# ltk-mw-tx.net
KiCad netlist of a schematic drawn in Altium Designer
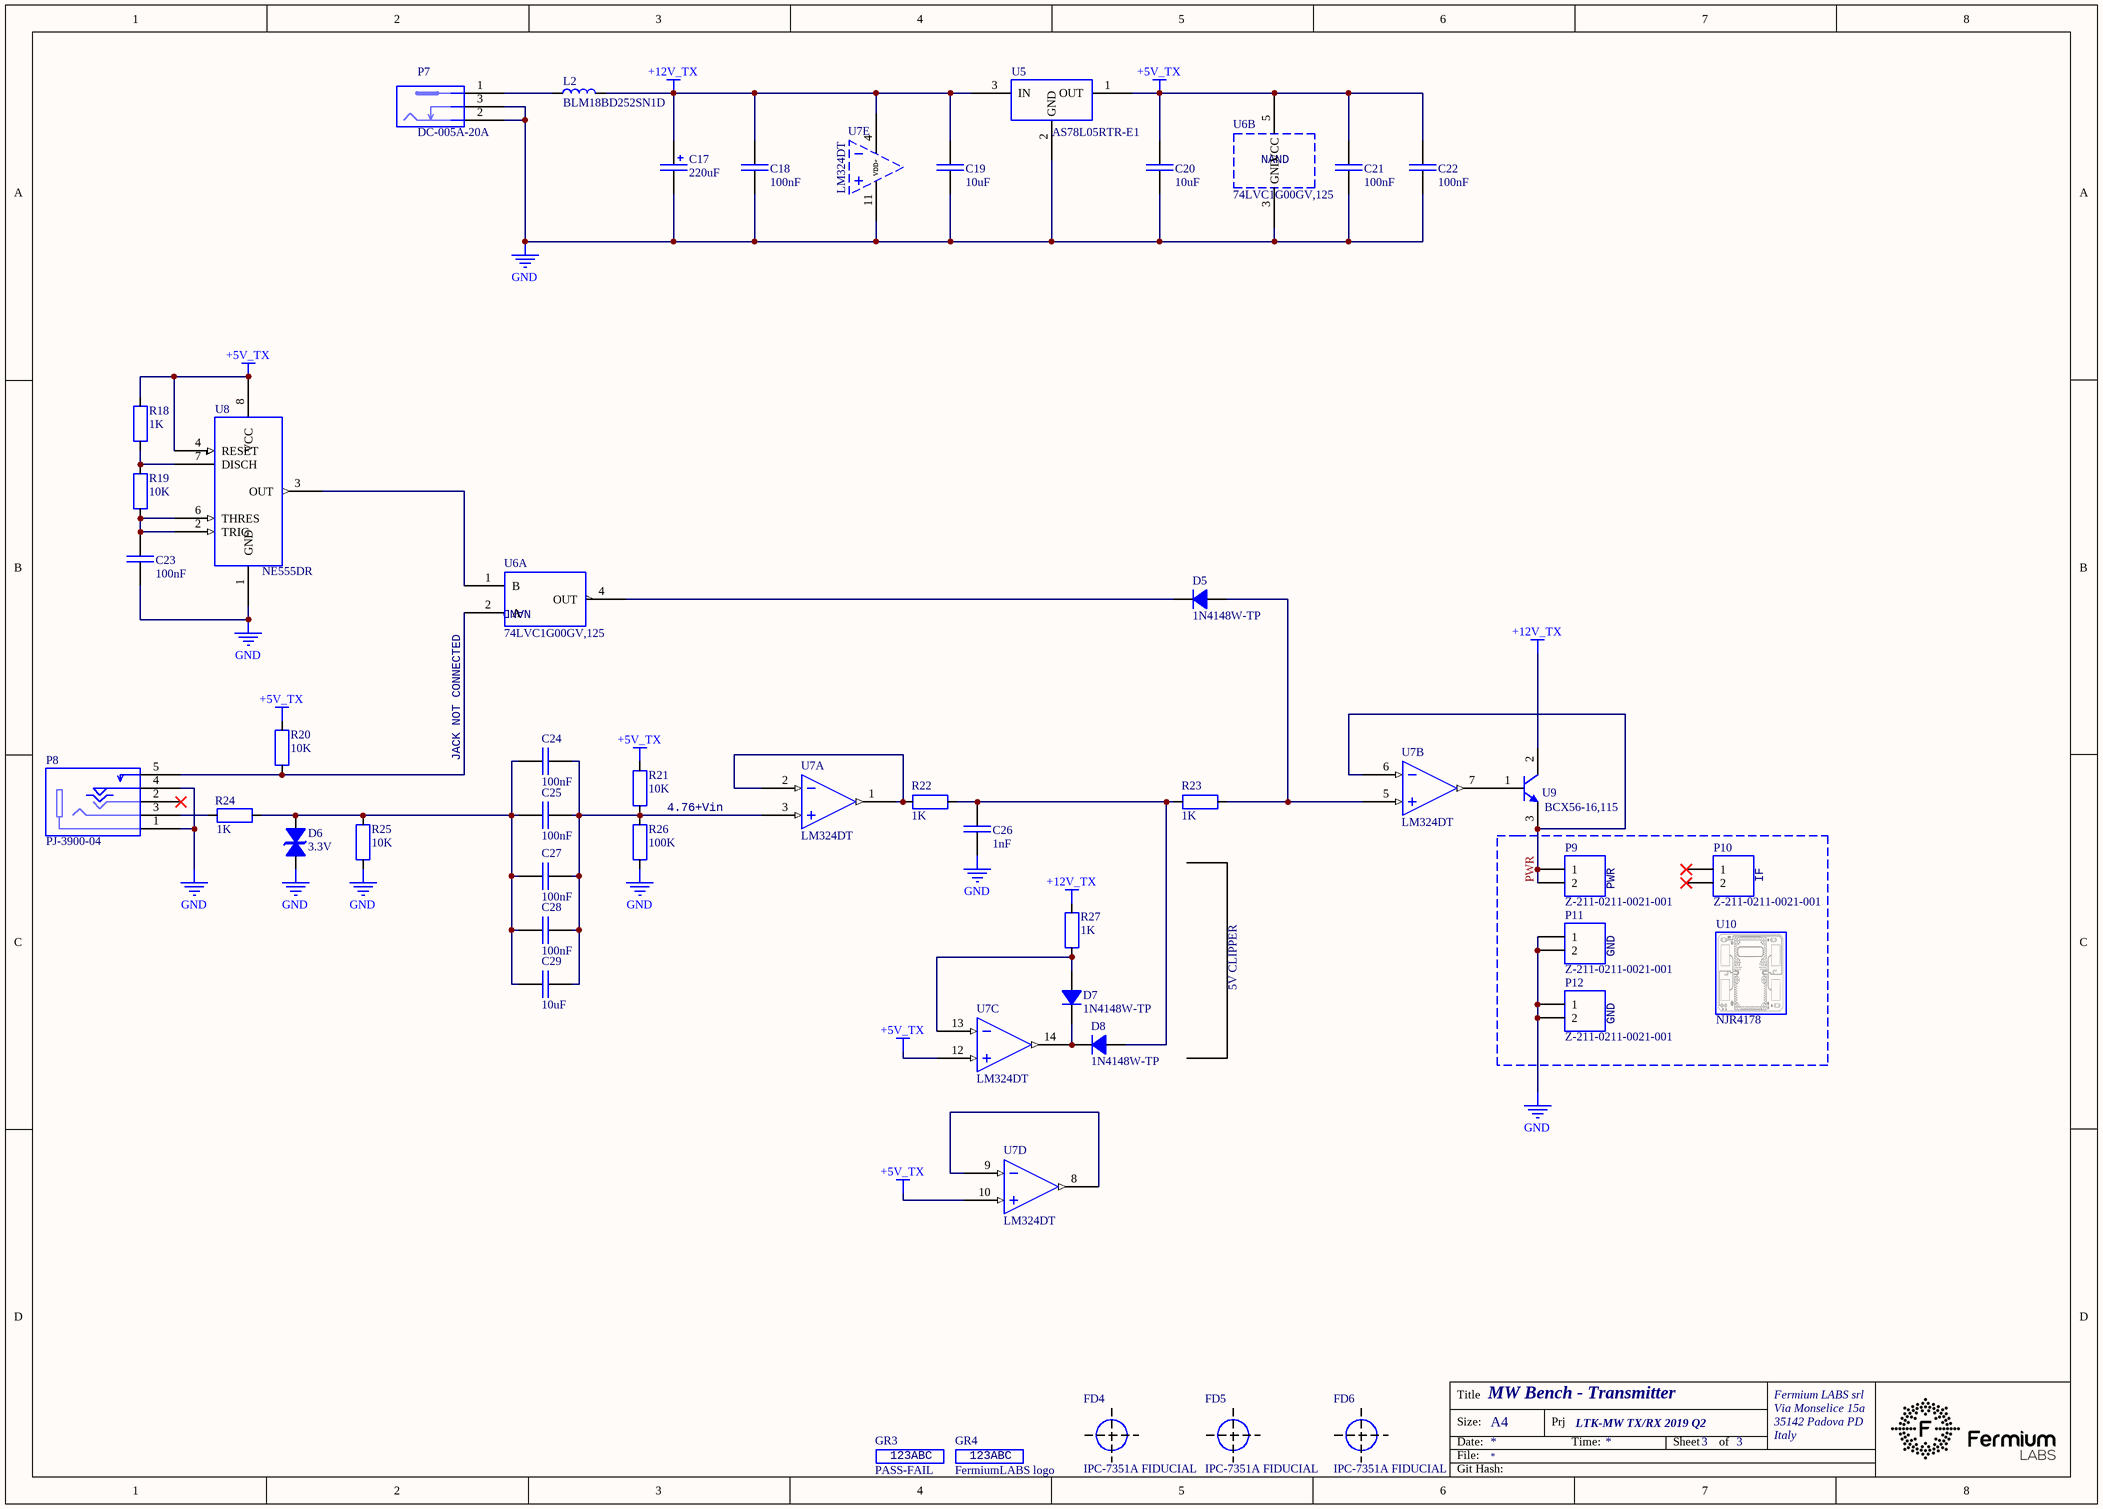
[diagram p0: ltk-mw-tx.SchDoc]

(export (version "E")
  (design (tool "Eeschema 10.0.6"))
  (components
    (comp (ref "C17")
      (value "220uF")
      (footprint "3924B366-8672-45E9-B0BE-62DACC24E783")
      (description "CAP  THT ELEC 220uF 25V 20%")
      (fields (field (name "PART NUMBER") "1a28df19-6d3e-4a71-836c-f22920f8e8ab"))
      (libsource (lib "frmdblib") (part "GENERIC_C_ELEC"))
    )
    (comp (ref "C18")
      (value "100nF")
      (footprint "CAP 0603_1608")
      (description "CAP SMD MLCC 100nF 25V 0603 X7R")
      (fields (field (name "PART NUMBER") "02841f84-ac15-41b5-9e17-915f8f067828"))
      (libsource (lib "frmdblib") (part "GENERIC_C"))
    )
    (comp (ref "C19")
      (value "10uF")
      (footprint "CAP 0805_2012")
      (description "CAP SMD MLCC 10uF 25V 0805 X5R")
      (fields (field (name "PART NUMBER") "1ffbe5a9-0884-4740-bdad-20a6a98400e6"))
      (libsource (lib "frmdblib") (part "GENERIC_C"))
    )
    (comp (ref "C20")
      (value "10uF")
      (footprint "CAP 0805_2012")
      (description "CAP SMD MLCC 10uF 25V 0805 X5R")
      (fields (field (name "PART NUMBER") "1ffbe5a9-0884-4740-bdad-20a6a98400e6"))
      (libsource (lib "frmdblib") (part "GENERIC_C"))
    )
    (comp (ref "C21")
      (value "100nF")
      (footprint "CAP 0603_1608")
      (description "CAP SMD MLCC 100nF 25V 0603 X7R")
      (fields (field (name "PART NUMBER") "02841f84-ac15-41b5-9e17-915f8f067828"))
      (libsource (lib "frmdblib") (part "GENERIC_C"))
    )
    (comp (ref "C22")
      (value "100nF")
      (footprint "CAP 0603_1608")
      (description "CAP SMD MLCC 100nF 25V 0603 X7R")
      (fields (field (name "PART NUMBER") "02841f84-ac15-41b5-9e17-915f8f067828"))
      (libsource (lib "frmdblib") (part "GENERIC_C"))
    )
    (comp (ref "C23")
      (value "100nF")
      (footprint "CAP 0603_1608")
      (description "CAP SMD MLCC 100nF 25V 0603 X7R")
      (fields (field (name "PART NUMBER") "02841f84-ac15-41b5-9e17-915f8f067828"))
      (libsource (lib "frmdblib") (part "GENERIC_C"))
    )
    (comp (ref "C24")
      (value "100nF")
      (footprint "CAP 0603_1608")
      (description "CAP SMD MLCC 100nF 25V 0603 X7R")
      (fields (field (name "PART NUMBER") "02841f84-ac15-41b5-9e17-915f8f067828"))
      (libsource (lib "frmdblib") (part "GENERIC_C"))
    )
    (comp (ref "C25")
      (value "100nF")
      (footprint "CAP 0603_1608")
      (description "CAP SMD MLCC 100nF 25V 0603 X7R")
      (fields (field (name "PART NUMBER") "02841f84-ac15-41b5-9e17-915f8f067828"))
      (libsource (lib "frmdblib") (part "GENERIC_C"))
    )
    (comp (ref "C26")
      (value "1nF")
      (footprint "CAP 0603_1608")
      (description "CAP SMD MLCC 1nF 50V 0603 X7R")
      (fields (field (name "PART NUMBER") "0eca2548-3630-4fea-a3d5-94248c1cae74"))
      (libsource (lib "frmdblib") (part "GENERIC_C"))
    )
    (comp (ref "C27")
      (value "100nF")
      (footprint "CAP 0603_1608")
      (description "CAP SMD MLCC 100nF 25V 0603 X7R")
      (fields (field (name "PART NUMBER") "02841f84-ac15-41b5-9e17-915f8f067828"))
      (libsource (lib "frmdblib") (part "GENERIC_C"))
    )
    (comp (ref "C28")
      (value "100nF")
      (footprint "CAP 0603_1608")
      (description "CAP SMD MLCC 100nF 25V 0603 X7R")
      (fields (field (name "PART NUMBER") "02841f84-ac15-41b5-9e17-915f8f067828"))
      (libsource (lib "frmdblib") (part "GENERIC_C"))
    )
    (comp (ref "C29")
      (value "10uF")
      (footprint "CAP 0805_2012")
      (description "CAP SMD MLCC 10uF 25V 0805 X5R")
      (fields (field (name "PART NUMBER") "1ffbe5a9-0884-4740-bdad-20a6a98400e6"))
      (libsource (lib "frmdblib") (part "GENERIC_C"))
    )
    (comp (ref "D5")
      (value "1N4148W-TP")
      (footprint "SOD-123")
      (description "DIODE SMD 100V 150mA 1.5Vf SOD-123 4148")
      (fields (field (name "PART NUMBER") "5e920700-75df-48e3-84dd-8f9f777caed8"))
      (libsource (lib "frmdblib") (part "GENERIC_D"))
    )
    (comp (ref "D6")
      (value "3.3V")
      (footprint "SOD523F")
      (description "DIODE SMD TVS 3.3V BIDIRECTIONAL SOD-523")
      (fields (field (name "PART NUMBER") "d6266fd0-7428-4fb9-a062-338cdce926fd"))
      (libsource (lib "frmdblib") (part "GENERIC_D_TVS_BI"))
    )
    (comp (ref "D7")
      (value "1N4148W-TP")
      (footprint "SOD-123")
      (description "DIODE SMD 100V 150mA 1.5Vf SOD-123 4148")
      (fields (field (name "PART NUMBER") "5e920700-75df-48e3-84dd-8f9f777caed8"))
      (libsource (lib "frmdblib") (part "GENERIC_D"))
    )
    (comp (ref "D8")
      (value "1N4148W-TP")
      (footprint "SOD-123")
      (description "DIODE SMD 100V 150mA 1.5Vf SOD-123 4148")
      (fields (field (name "PART NUMBER") "5e920700-75df-48e3-84dd-8f9f777caed8"))
      (libsource (lib "frmdblib") (part "GENERIC_D"))
    )
    (comp (ref "FD4")
      (value "IPC-7351A FIDUCIAL")
      (footprint "FIDUCIAL-IPC-7351A")
      (description "GRAPHICS FIDUCIAL IPC-7351A")
      (fields (field (name "PART NUMBER") "19da4612-eb95-43bb-9984-553a52b2a224"))
      (libsource (lib "frmdblib") (part "GENERIC_FIDUCIAL"))
    )
    (comp (ref "FD5")
      (value "IPC-7351A FIDUCIAL")
      (footprint "FIDUCIAL-IPC-7351A")
      (description "GRAPHICS FIDUCIAL IPC-7351A")
      (fields (field (name "PART NUMBER") "19da4612-eb95-43bb-9984-553a52b2a224"))
      (libsource (lib "frmdblib") (part "GENERIC_FIDUCIAL"))
    )
    (comp (ref "FD6")
      (value "IPC-7351A FIDUCIAL")
      (footprint "FIDUCIAL-IPC-7351A")
      (description "GRAPHICS FIDUCIAL IPC-7351A")
      (fields (field (name "PART NUMBER") "19da4612-eb95-43bb-9984-553a52b2a224"))
      (libsource (lib "frmdblib") (part "GENERIC_FIDUCIAL"))
    )
    (comp (ref "GR3")
      (value "PASS-FAIL")
      (footprint "0B1556B7-A534-4801-B57D-01EFA34B1205")
      (description "GRAPHICS PASS-FAIL MARK")
      (fields (field (name "PART NUMBER") "d1abe19f-3fed-4f20-b2ed-afc0ffbc6628"))
      (libsource (lib "frmdblib") (part "GENERIC_GRAPHIC"))
    )
    (comp (ref "GR4")
      (value "FermiumLABS logo")
      (footprint "5394DE47-A0E8-4329-8464-7791B7C19310")
      (description "GRAPHICS LOGO FERMIUM LABS SRL")
      (fields (field (name "PART NUMBER") "50f8ea88-0034-49fe-a263-d8e97bc35e2f"))
      (libsource (lib "frmdblib") (part "GENERIC_GRAPHIC"))
    )
    (comp (ref "L2")
      (value "BLM18BD252SN1D")
      (footprint "FER 0603_1608")
      (description "FER SMD CHIP 0603 400mA 1k@100MHz 500mOhm")
      (fields (field (name "PART NUMBER") "c9e30ae8-9d5b-4135-a079-b1147da846d8"))
      (libsource (lib "frmdblib") (part "GENERIC_L"))
    )
    (comp (ref "P7")
      (value "DC-005A-20A")
      (footprint "F0972D8A-C5C0-4A84-836D-A9666EE65C2D")
      (description "CONN THT DC JACK 0.5A 30VDC 5Kcycles")
      (fields (field (name "PART NUMBER") "b53db51a-1725-412b-9039-fa7a45c7c438"))
      (libsource (lib "frmdblib") (part "34A1CD0B-E262-46EF-B9F1-39CB809C308F"))
    )
    (comp (ref "P8")
      (value "PJ-3900-04")
      (footprint "7EF2B92C-0FC9-4C85-B662-5CEC65BFCCC4")
      (description "CONN THT 3.5mm AUDIO STEREO AUX SWITCH")
      (fields (field (name "PART NUMBER") "80507a24-5d7c-4cf5-953e-f54832d54564"))
      (libsource (lib "frmdblib") (part "46E41D2F-79BD-46AC-B778-70B2D50A946A"))
    )
    (comp (ref "P9")
      (value "Z-211-0211-0021-001")
      (footprint "0FBEB40D-2B6D-43C7-945F-A2D40A82B953")
      (description "CONN THT PIN HEADER 2P MALE 2.54mm")
      (fields (field (name "PART NUMBER") "fb9043ef-1dd5-4a9c-8c1a-da0c667690ac"))
      (libsource (lib "frmdblib") (part "Header 2"))
    )
    (comp (ref "P10")
      (value "Z-211-0211-0021-001")
      (footprint "0FBEB40D-2B6D-43C7-945F-A2D40A82B953")
      (description "CONN THT PIN HEADER 2P MALE 2.54mm")
      (fields (field (name "PART NUMBER") "fb9043ef-1dd5-4a9c-8c1a-da0c667690ac"))
      (libsource (lib "frmdblib") (part "Header 2"))
    )
    (comp (ref "P11")
      (value "Z-211-0211-0021-001")
      (footprint "0FBEB40D-2B6D-43C7-945F-A2D40A82B953")
      (description "CONN THT PIN HEADER 2P MALE 2.54mm")
      (fields (field (name "PART NUMBER") "fb9043ef-1dd5-4a9c-8c1a-da0c667690ac"))
      (libsource (lib "frmdblib") (part "Header 2"))
    )
    (comp (ref "P12")
      (value "Z-211-0211-0021-001")
      (footprint "0FBEB40D-2B6D-43C7-945F-A2D40A82B953")
      (description "CONN THT PIN HEADER 2P MALE 2.54mm")
      (fields (field (name "PART NUMBER") "fb9043ef-1dd5-4a9c-8c1a-da0c667690ac"))
      (libsource (lib "frmdblib") (part "Header 2"))
    )
    (comp (ref "R18")
      (value "1K")
      (footprint "RES 0603_1608")
      (description "RES SMD 1K OHM 1% 1/10W 0603")
      (fields (field (name "PART NUMBER") "a678220f-9e9d-4863-a833-9993504f723c"))
      (libsource (lib "frmdblib") (part "GENERIC_R"))
    )
    (comp (ref "R19")
      (value "10K")
      (footprint "RES 0603_1608")
      (description "RES SMD 10K OHM 1% 1/10W 0603")
      (fields (field (name "PART NUMBER") "93242766-ba1d-462d-b58f-ce1dfc4129c8"))
      (libsource (lib "frmdblib") (part "GENERIC_R"))
    )
    (comp (ref "R20")
      (value "10K")
      (footprint "RES 0603_1608")
      (description "RES SMD 10K OHM 1% 1/10W 0603")
      (fields (field (name "PART NUMBER") "93242766-ba1d-462d-b58f-ce1dfc4129c8"))
      (libsource (lib "frmdblib") (part "GENERIC_R"))
    )
    (comp (ref "R21")
      (value "10K")
      (footprint "RES 0603_1608")
      (description "RES SMD 10K OHM 1% 1/10W 0603")
      (fields (field (name "PART NUMBER") "93242766-ba1d-462d-b58f-ce1dfc4129c8"))
      (libsource (lib "frmdblib") (part "GENERIC_R"))
    )
    (comp (ref "R22")
      (value "1K")
      (footprint "RES 0603_1608")
      (description "RES SMD 1K OHM 1% 1/10W 0603")
      (fields (field (name "PART NUMBER") "a678220f-9e9d-4863-a833-9993504f723c"))
      (libsource (lib "frmdblib") (part "GENERIC_R"))
    )
    (comp (ref "R23")
      (value "1K")
      (footprint "RES 0603_1608")
      (description "RES SMD 1K OHM 1% 1/10W 0603")
      (fields (field (name "PART NUMBER") "a678220f-9e9d-4863-a833-9993504f723c"))
      (libsource (lib "frmdblib") (part "GENERIC_R"))
    )
    (comp (ref "R24")
      (value "1K")
      (footprint "RES 0603_1608")
      (description "RES SMD 1K OHM 1% 1/10W 0603")
      (fields (field (name "PART NUMBER") "a678220f-9e9d-4863-a833-9993504f723c"))
      (libsource (lib "frmdblib") (part "GENERIC_R"))
    )
    (comp (ref "R25")
      (value "10K")
      (footprint "RES 0603_1608")
      (description "RES SMD 10K OHM 1% 1/10W 0603")
      (fields (field (name "PART NUMBER") "93242766-ba1d-462d-b58f-ce1dfc4129c8"))
      (libsource (lib "frmdblib") (part "GENERIC_R"))
    )
    (comp (ref "R26")
      (value "100K")
      (footprint "RES 0603_1608")
      (description "RES SMD 100K OHM 1% 1/10W 0603")
      (fields (field (name "PART NUMBER") "76af10b3-9d85-4b5c-a2d6-26cc74f432f7"))
      (libsource (lib "frmdblib") (part "GENERIC_R"))
    )
    (comp (ref "R27")
      (value "1K")
      (footprint "RES 0603_1608")
      (description "RES SMD 1K OHM 1% 1/10W 0603")
      (fields (field (name "PART NUMBER") "a678220f-9e9d-4863-a833-9993504f723c"))
      (libsource (lib "frmdblib") (part "GENERIC_R"))
    )
    (comp (ref "U5")
      (value "AS78L05RTR-E1")
      (footprint "E733EFB9-FE91-4AE9-9197-29251971C3DC")
      (description "IC SMD LINEAR VOLTAGE REGULATOR 5V 100mA SOT-89")
      (fields (field (name "PART NUMBER") "fd64863e-487f-4688-b264-696c0ba5456b"))
      (libsource (lib "frmdblib") (part "FCB39772-D6AF-4D61-BC58-A46A50428B6B"))
    )
    (comp (ref "U6")
      (value "74LVC1G00GV,125")
      (footprint "9B4F62E8-D129-4139-99C7-3E5580D0C4B3")
      (description "IC SMD NAND GATE 2 INPUTS 74X00 SC-74A")
      (fields (field (name "PART NUMBER") "33900555-dbb4-4b72-871f-952983a59b08"))
      (libsource (lib "frmdblib") (part "2A82CEC3-2DF5-4DD3-9AA0-8AD0F8FDAF27"))
    )
    (comp (ref "U7")
      (value "LM324DT")
      (footprint "34355DA5-B1DA-47C2-A88A-ECF82120A4F7")
      (description "IC SMD OPAMP LM324DT SO-14")
      (fields (field (name "PART NUMBER") "21a85167-c328-42f7-a52e-365842c6dad3"))
      (libsource (lib "frmdblib") (part "B8DB4B19-8E9C-4F46-A390-7A352E041443"))
    )
    (comp (ref "U8")
      (value "NE555DR")
      (footprint "TI SOIC-8 D")
      (description "IC SMD TIMER NE555 SOIC-8")
      (fields (field (name "PART NUMBER") "d16ab88a-2543-469a-8940-7b800b633548"))
      (libsource (lib "frmdblib") (part "3A1FF759-9FC3-4379-AD1F-76F749A75FB1"))
    )
    (comp (ref "U9")
      (value "BCX56-16,115")
      (footprint "13DB0D7C-893C-4A10-A75B-EAAEE46B398C")
      (description "TRANS NPN BCX56-16 1A 80V 1.25W SOT-89-3")
      (fields (field (name "PART NUMBER") "0e502e05-00ae-4c6f-83a4-b2f55de2403a"))
      (libsource (lib "frmdblib") (part "GENERIC_NPN_BCE"))
    )
    (comp (ref "U10")
      (value "NJR4178")
      (footprint "25B19271-CD6F-4BC8-A99B-F617D566DC9C")
      (description "MODULE THT RADAR DOPPLER 10.525GHz NJR4178")
      (fields (field (name "PART NUMBER") "f0e19a38-18de-4253-8da2-aebb0c4083bd"))
      (libsource (lib "frmdblib") (part "687D5558-C857-4646-9F75-B643D2B4D9DF"))
    )
  )
  (nets
    (net (code "1") (name "+5V_TX") (class "Default")
      (node (ref "C20") (pin "2") (pintype "passive"))
      (node (ref "C21") (pin "2") (pintype "passive"))
      (node (ref "C22") (pin "2") (pintype "passive"))
      (node (ref "R18") (pin "2") (pintype "passive"))
      (node (ref "R20") (pin "1") (pintype "passive"))
      (node (ref "R21") (pin "2") (pintype "passive"))
      (node (ref "U5") (pin "1") (pinfunction "OUT_1") (pintype "passive"))
      (node (ref "U6") (pin "5") (pinfunction "VCC_5") (pintype "passive"))
      (node (ref "U7") (pin "10") (pinfunction "IN+_10") (pintype "input"))
      (node (ref "U7") (pin "12") (pinfunction "IN+_12") (pintype "input"))
      (node (ref "U8") (pin "4") (pinfunction "RESET_4") (pintype "input"))
      (node (ref "U8") (pin "8") (pinfunction "VCC_8") (pintype "power_in"))
    )
    (net (code "2") (name "+12V_TX") (class "Default")
      (node (ref "C17") (pin "1") (pintype "passive"))
      (node (ref "C18") (pin "2") (pintype "passive"))
      (node (ref "C19") (pin "2") (pintype "passive"))
      (node (ref "L2") (pin "2") (pintype "passive"))
      (node (ref "R27") (pin "2") (pintype "passive"))
      (node (ref "U5") (pin "3") (pinfunction "IN_3") (pintype "passive"))
      (node (ref "U7") (pin "4") (pinfunction "VDD+_4") (pintype "power_in"))
      (node (ref "U9") (pin "2") (pinfunction "C_2") (pintype "passive"))
    )
    (net (code "3") (name "/PWR") (class "Default")
      (node (ref "P9") (pin "1") (pinfunction "1_1") (pintype "passive"))
      (node (ref "P9") (pin "2") (pinfunction "2_2") (pintype "passive"))
      (node (ref "U7") (pin "6") (pinfunction "IN-_6") (pintype "input"))
      (node (ref "U9") (pin "3") (pinfunction "E_3") (pintype "passive"))
    )
    (net (code "4") (name "GND") (class "Default")
      (node (ref "C17") (pin "2") (pintype "passive"))
      (node (ref "C18") (pin "1") (pintype "passive"))
      (node (ref "C19") (pin "1") (pintype "passive"))
      (node (ref "C20") (pin "1") (pintype "passive"))
      (node (ref "C21") (pin "1") (pintype "passive"))
      (node (ref "C22") (pin "1") (pintype "passive"))
      (node (ref "C23") (pin "2") (pintype "passive"))
      (node (ref "C26") (pin "2") (pintype "passive"))
      (node (ref "D6") (pin "2") (pintype "passive"))
      (node (ref "P11") (pin "1") (pinfunction "1_1") (pintype "passive"))
      (node (ref "P11") (pin "2") (pinfunction "2_2") (pintype "passive"))
      (node (ref "P12") (pin "1") (pinfunction "1_1") (pintype "passive"))
      (node (ref "P12") (pin "2") (pinfunction "2_2") (pintype "passive"))
      (node (ref "P7") (pin "2") (pinfunction "2_2") (pintype "passive"))
      (node (ref "P7") (pin "3") (pinfunction "3_3") (pintype "passive"))
      (node (ref "P8") (pin "1") (pinfunction "GND_1") (pintype "passive"))
      (node (ref "P8") (pin "4") (pinfunction "AUX_4") (pintype "passive"))
      (node (ref "R25") (pin "1") (pintype "passive"))
      (node (ref "R26") (pin "1") (pintype "passive"))
      (node (ref "U5") (pin "2") (pinfunction "GND_2") (pintype "passive"))
      (node (ref "U6") (pin "3") (pinfunction "GND_3") (pintype "passive"))
      (node (ref "U7") (pin "11") (pinfunction "VDD-_11") (pintype "power_in"))
      (node (ref "U8") (pin "1") (pinfunction "GND_1") (pintype "power_in"))
    )
    (net (code "5") (name "Net-(C24-Pad1)") (class "Default")
      (node (ref "C24") (pin "1") (pintype "passive"))
      (node (ref "C25") (pin "1") (pintype "passive"))
      (node (ref "C27") (pin "1") (pintype "passive"))
      (node (ref "C28") (pin "1") (pintype "passive"))
      (node (ref "C29") (pin "1") (pintype "passive"))
      (node (ref "D6") (pin "1") (pintype "passive"))
      (node (ref "R24") (pin "1") (pintype "passive"))
      (node (ref "R25") (pin "2") (pintype "passive"))
    )
    (net (code "6") (name "Net-(D5-A)") (class "Default")
      (node (ref "D5") (pin "2") (pinfunction "A_2") (pintype "passive"))
      (node (ref "R23") (pin "2") (pintype "passive"))
      (node (ref "U7") (pin "5") (pinfunction "IN+_5") (pintype "input"))
    )
    (net (code "7") (name "Net-(D5-K)") (class "Default")
      (node (ref "D5") (pin "1") (pinfunction "K_1") (pintype "passive"))
      (node (ref "U6") (pin "4") (pinfunction "OUT_4") (pintype "passive"))
    )
    (net (code "8") (name "Net-(D7-A)") (class "Default")
      (node (ref "D7") (pin "2") (pinfunction "A_2") (pintype "passive"))
      (node (ref "R27") (pin "1") (pintype "passive"))
      (node (ref "U7") (pin "13") (pinfunction "IN-_13") (pintype "input"))
    )
    (net (code "9") (name "Net-(D7-K)") (class "Default")
      (node (ref "D7") (pin "1") (pinfunction "K_1") (pintype "passive"))
      (node (ref "D8") (pin "1") (pinfunction "K_1") (pintype "passive"))
      (node (ref "U7") (pin "14") (pinfunction "OUT_14") (pintype "output"))
    )
    (net (code "10") (name "Net-(D8-A)") (class "Default")
      (node (ref "C26") (pin "1") (pintype "passive"))
      (node (ref "D8") (pin "2") (pinfunction "A_2") (pintype "passive"))
      (node (ref "R22") (pin "2") (pintype "passive"))
      (node (ref "R23") (pin "1") (pintype "passive"))
    )
    (net (code "11") (name "Net-(L2-Pad1)") (class "Default")
      (node (ref "L2") (pin "1") (pintype "passive"))
      (node (ref "P7") (pin "1") (pinfunction "1_1") (pintype "passive"))
    )
    (net (code "12") (name "Net-(P8-L)") (class "Default")
      (node (ref "P8") (pin "3") (pinfunction "L_3") (pintype "passive"))
      (node (ref "R24") (pin "2") (pintype "passive"))
    )
    (net (code "13") (name "Net-(U6A-A)") (class "Default")
      (node (ref "P8") (pin "5") (pinfunction "AUX_5") (pintype "passive"))
      (node (ref "R20") (pin "2") (pintype "passive"))
      (node (ref "U6") (pin "2") (pinfunction "A_2") (pintype "passive"))
    )
    (net (code "14") (name "Net-(U6A-B)") (class "Default")
      (node (ref "U6") (pin "1") (pinfunction "B_1") (pintype "passive"))
      (node (ref "U8") (pin "3") (pinfunction "OUT_3") (pintype "output"))
    )
    (net (code "15") (name "Net-(U7A-IN+)") (class "Default")
      (node (ref "C24") (pin "2") (pintype "passive"))
      (node (ref "C25") (pin "2") (pintype "passive"))
      (node (ref "C27") (pin "2") (pintype "passive"))
      (node (ref "C28") (pin "2") (pintype "passive"))
      (node (ref "C29") (pin "2") (pintype "passive"))
      (node (ref "R21") (pin "1") (pintype "passive"))
      (node (ref "R26") (pin "2") (pintype "passive"))
      (node (ref "U7") (pin "3") (pinfunction "IN+_3") (pintype "input"))
    )
    (net (code "16") (name "Net-(U7A-IN-)") (class "Default")
      (node (ref "R22") (pin "1") (pintype "passive"))
      (node (ref "U7") (pin "1") (pinfunction "OUT_1") (pintype "output"))
      (node (ref "U7") (pin "2") (pinfunction "IN-_2") (pintype "input"))
    )
    (net (code "17") (name "Net-(U7B-OUT)") (class "Default")
      (node (ref "U7") (pin "7") (pinfunction "OUT_7") (pintype "output"))
      (node (ref "U9") (pin "1") (pinfunction "B_1") (pintype "passive"))
    )
    (net (code "18") (name "Net-(U7D-IN-)") (class "Default")
      (node (ref "U7") (pin "8") (pinfunction "OUT_8") (pintype "output"))
      (node (ref "U7") (pin "9") (pinfunction "IN-_9") (pintype "input"))
    )
    (net (code "19") (name "Net-(U8-DISCH)") (class "Default")
      (node (ref "R18") (pin "1") (pintype "passive"))
      (node (ref "R19") (pin "2") (pintype "passive"))
      (node (ref "U8") (pin "7") (pinfunction "DISCH_7") (pintype "passive"))
    )
    (net (code "20") (name "Net-(U8-THRES)") (class "Default")
      (node (ref "C23") (pin "1") (pintype "passive"))
      (node (ref "R19") (pin "1") (pintype "passive"))
      (node (ref "U8") (pin "2") (pinfunction "TRIG_2") (pintype "input"))
      (node (ref "U8") (pin "6") (pinfunction "THRES_6") (pintype "input"))
    )
    (net (code "21") (name "unconnected-(P8-R-Pad2)") (class "Default")
      (node (ref "P8") (pin "2") (pinfunction "R_2") (pintype "passive+no_connect"))
    )
    (net (code "22") (name "unconnected-(P10-Pad1)") (class "Default")
      (node (ref "P10") (pin "1") (pinfunction "1_1") (pintype "passive+no_connect"))
    )
    (net (code "23") (name "unconnected-(P10-Pad2)") (class "Default")
      (node (ref "P10") (pin "2") (pinfunction "2_2") (pintype "passive+no_connect"))
    )
  )
)
